# Processor.net
KiCad netlist of a schematic drawn in Altium Designer
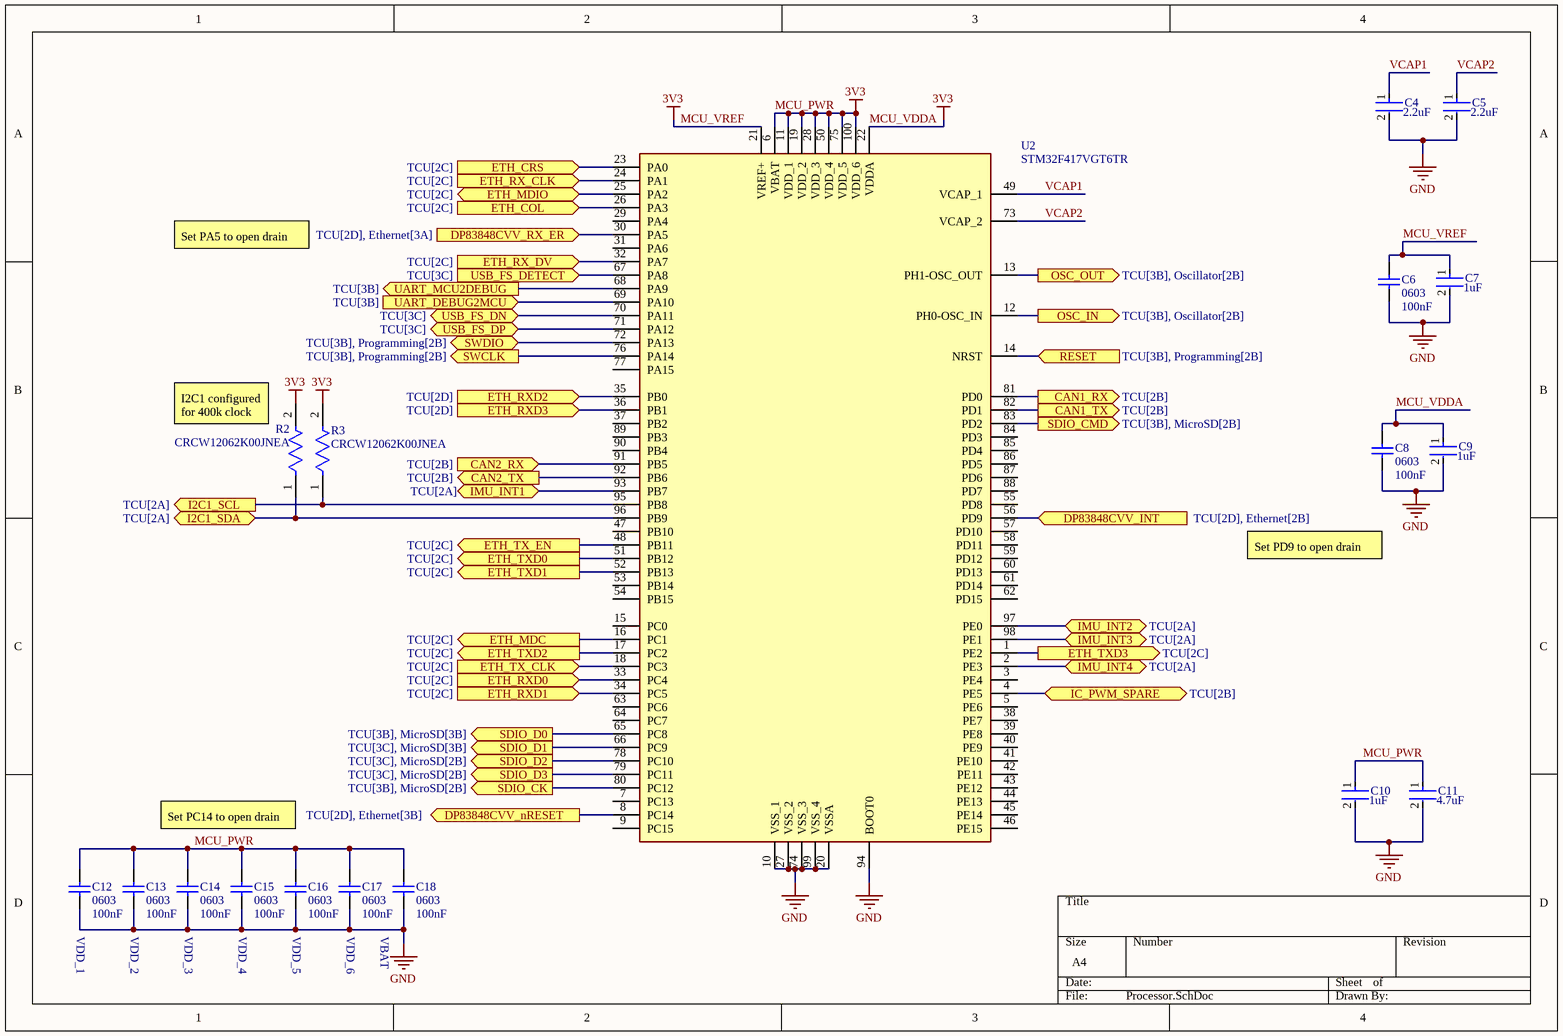
[diagram p0: Processor.SchDoc]

(export (version "E")
  (design (tool "Eeschema 10.0.6"))
  (components
    (comp (ref "C4")
      (value "C0603C225K4PACTU")
      (footprint "FP-C0603C225K4PACTU-MFG")
      (description "CAP CER 2.2UF 16V X5R 0603")
      (fields
        (field (name "CAPACITANCE") "2.2uF")
        (field (name "TOLERANCE") "10%")
        (field (name "VOLTAGE") "16V")
      )
      (libsource (lib "Altium Content Vault") (part "b4654b650e69147ec39a6b967a45e02"))
    )
    (comp (ref "C5")
      (value "C0603C225K4PACTU")
      (footprint "FP-C0603C225K4PACTU-MFG")
      (description "CAP CER 2.2UF 16V X5R 0603")
      (fields
        (field (name "CAPACITANCE") "2.2uF")
        (field (name "TOLERANCE") "10%")
        (field (name "VOLTAGE") "16V")
      )
      (libsource (lib "Altium Content Vault") (part "b4654b650e69147ec39a6b967a45e02"))
    )
    (comp (ref "C6")
      (value "C0603X104K5RACTU")
      (footprint "CAPC1608X87X35NL15T15")
      (fields
        (field (name "MANUFACTURER") "Kemet")
        (field (name "CASE CODE (IMPERIAL)") "0603")
        (field (name "CAPACITANCE") "100nF")
        (field (name "TOLERANCE") "10%")
        (field (name "VOLTAGE") "50V")
      )
      (libsource (lib "Altium Content Vault") (part "CAP"))
    )
    (comp (ref "C7")
      (value "CL10A105KA8NNNC")
      (footprint "FP-CL10-IPC_C")
      (description "Cap Ceramic 1uF 25V X5R ±10% Pad SMD 0603 +85°C T/R")
      (fields
        (field (name "CAPACITANCE") "1uF")
        (field (name "VOLTAGE") "25V")
        (field (name "TOLERANCE") "10%")
      )
      (libsource (lib "Altium Content Vault") (part "b4654b650e69147ec39a6b967a45e02"))
    )
    (comp (ref "C8")
      (value "C0603X104K5RACTU")
      (footprint "CAPC1608X87X35NL15T15")
      (fields
        (field (name "MANUFACTURER") "Kemet")
        (field (name "CASE CODE (IMPERIAL)") "0603")
        (field (name "CAPACITANCE") "100nF")
        (field (name "TOLERANCE") "10%")
        (field (name "VOLTAGE") "50V")
      )
      (libsource (lib "Altium Content Vault") (part "CAP"))
    )
    (comp (ref "C9")
      (value "CL10A105KA8NNNC")
      (footprint "FP-CL10-IPC_C")
      (description "Cap Ceramic 1uF 25V X5R ±10% Pad SMD 0603 +85°C T/R")
      (fields
        (field (name "CAPACITANCE") "1uF")
        (field (name "VOLTAGE") "25V")
        (field (name "TOLERANCE") "10%")
      )
      (libsource (lib "Altium Content Vault") (part "b4654b650e69147ec39a6b967a45e02"))
    )
    (comp (ref "C10")
      (value "CL10A105KA8NNNC")
      (footprint "FP-CL10-IPC_C")
      (description "Cap Ceramic 1uF 25V X5R ±10% Pad SMD 0603 +85°C T/R")
      (fields
        (field (name "CAPACITANCE") "1uF")
        (field (name "VOLTAGE") "25V")
        (field (name "TOLERANCE") "10%")
      )
      (libsource (lib "Altium Content Vault") (part "b4654b650e69147ec39a6b967a45e02"))
    )
    (comp (ref "C11")
      (value "C1005X5R1A475K050BC")
      (footprint "FP-C1005-050-0_15-MFG")
      (description "CAP CER 4.7UF 10V X5R 0402")
      (fields (field (name "TOLERANCE") "10%") (field (name "CAPACITANCE") "4.7uF"))
      (libsource (lib "Altium Content Vault") (part "b4654b650e69147ec39a6b967a45e02"))
    )
    (comp (ref "C12")
      (value "C0603X104K5RACTU")
      (footprint "CAPC1608X87X35NL15T15")
      (fields
        (field (name "MANUFACTURER") "Kemet")
        (field (name "CASE CODE (IMPERIAL)") "0603")
        (field (name "CAPACITANCE") "100nF")
        (field (name "TOLERANCE") "10%")
        (field (name "VOLTAGE") "50V")
      )
      (libsource (lib "Altium Content Vault") (part "CAP"))
    )
    (comp (ref "C13")
      (value "C0603X104K5RACTU")
      (footprint "CAPC1608X87X35NL15T15")
      (fields
        (field (name "MANUFACTURER") "Kemet")
        (field (name "CASE CODE (IMPERIAL)") "0603")
        (field (name "CAPACITANCE") "100nF")
        (field (name "TOLERANCE") "10%")
        (field (name "VOLTAGE") "50V")
      )
      (libsource (lib "Altium Content Vault") (part "CAP"))
    )
    (comp (ref "C14")
      (value "C0603X104K5RACTU")
      (footprint "CAPC1608X87X35NL15T15")
      (fields
        (field (name "MANUFACTURER") "Kemet")
        (field (name "CASE CODE (IMPERIAL)") "0603")
        (field (name "CAPACITANCE") "100nF")
        (field (name "TOLERANCE") "10%")
        (field (name "VOLTAGE") "50V")
      )
      (libsource (lib "Altium Content Vault") (part "CAP"))
    )
    (comp (ref "C15")
      (value "C0603X104K5RACTU")
      (footprint "CAPC1608X87X35NL15T15")
      (fields
        (field (name "MANUFACTURER") "Kemet")
        (field (name "CASE CODE (IMPERIAL)") "0603")
        (field (name "CAPACITANCE") "100nF")
        (field (name "TOLERANCE") "10%")
        (field (name "VOLTAGE") "50V")
      )
      (libsource (lib "Altium Content Vault") (part "CAP"))
    )
    (comp (ref "C16")
      (value "C0603X104K5RACTU")
      (footprint "CAPC1608X87X35NL15T15")
      (fields
        (field (name "MANUFACTURER") "Kemet")
        (field (name "CASE CODE (IMPERIAL)") "0603")
        (field (name "CAPACITANCE") "100nF")
        (field (name "TOLERANCE") "10%")
        (field (name "VOLTAGE") "50V")
      )
      (libsource (lib "Altium Content Vault") (part "CAP"))
    )
    (comp (ref "C17")
      (value "C0603X104K5RACTU")
      (footprint "CAPC1608X87X35NL15T15")
      (fields
        (field (name "MANUFACTURER") "Kemet")
        (field (name "CASE CODE (IMPERIAL)") "0603")
        (field (name "CAPACITANCE") "100nF")
        (field (name "TOLERANCE") "10%")
        (field (name "VOLTAGE") "50V")
      )
      (libsource (lib "Altium Content Vault") (part "CAP"))
    )
    (comp (ref "C18")
      (value "C0603X104K5RACTU")
      (footprint "CAPC1608X87X35NL15T15")
      (fields
        (field (name "MANUFACTURER") "Kemet")
        (field (name "CASE CODE (IMPERIAL)") "0603")
        (field (name "CAPACITANCE") "100nF")
        (field (name "TOLERANCE") "10%")
        (field (name "VOLTAGE") "50V")
      )
      (libsource (lib "Altium Content Vault") (part "CAP"))
    )
    (comp (ref "R2")
      (value "CRCW12062K00JNEA")
      (footprint "FP-CRCW1206-e3-IPC_B")
      (description "RES Thick Film, 2kΩ, 5%, 0.25W, 200ppm/°C, 1206")
      (fields (field (name "TOLERANCE") "5%"))
      (libsource (lib "Altium Content Vault") (part "1029c3af85768c4190bb7ad29bc67b5"))
    )
    (comp (ref "R3")
      (value "CRCW12062K00JNEA")
      (footprint "FP-CRCW1206-e3-IPC_B")
      (description "RES Thick Film, 2kΩ, 5%, 0.25W, 200ppm/°C, 1206")
      (fields (field (name "TOLERANCE") "5%"))
      (libsource (lib "Altium Content Vault") (part "1029c3af85768c4190bb7ad29bc67b5"))
    )
    (comp (ref "U2")
      (value "STM32F417VGT6TR")
      (footprint "STM-LQFP100_N")
      (description "RISC Microcontroller, 32-Bit, FLASH, CORTEX-M4 CPU, 168MHz, CMOS, PQFP100")
      (fields (field (name "MANUFACTURER") "STMicroelectronics"))
      (libsource (lib "Microcontrollers") (part "STM32F417VGT6TR"))
    )
  )
  (nets
    (net (code "1") (name "/CAN1_RX") (class "Default")
      (node (ref "U2") (pin "81") (pinfunction "PD0_81") (pintype "passive"))
    )
    (net (code "2") (name "/CAN1_TX") (class "Default")
      (node (ref "U2") (pin "82") (pinfunction "PD1_82") (pintype "passive"))
    )
    (net (code "3") (name "/CAN2_RX") (class "Default")
      (node (ref "U2") (pin "91") (pinfunction "PB5_91") (pintype "passive"))
    )
    (net (code "4") (name "/CAN2_TX") (class "Default")
      (node (ref "U2") (pin "92") (pinfunction "PB6_92") (pintype "passive"))
    )
    (net (code "5") (name "/DP83848CVV_INT") (class "Default")
      (node (ref "U2") (pin "56") (pinfunction "PD9_56") (pintype "passive"))
    )
    (net (code "6") (name "/DP83848CVV_RX_ER") (class "Default")
      (node (ref "U2") (pin "30") (pinfunction "PA5_30") (pintype "passive"))
    )
    (net (code "7") (name "/DP83848CVV_nRESET") (class "Default")
      (node (ref "U2") (pin "8") (pinfunction "PC14_8") (pintype "passive"))
    )
    (net (code "8") (name "/ETH_COL") (class "Default")
      (node (ref "U2") (pin "26") (pinfunction "PA3_26") (pintype "passive"))
    )
    (net (code "9") (name "/ETH_CRS") (class "Default")
      (node (ref "U2") (pin "23") (pinfunction "PA0_23") (pintype "passive"))
    )
    (net (code "10") (name "/ETH_MDC") (class "Default")
      (node (ref "U2") (pin "16") (pinfunction "PC1_16") (pintype "passive"))
    )
    (net (code "11") (name "/ETH_MDIO") (class "Default")
      (node (ref "U2") (pin "25") (pinfunction "PA2_25") (pintype "passive"))
    )
    (net (code "12") (name "/ETH_RXD0") (class "Default")
      (node (ref "U2") (pin "33") (pinfunction "PC4_33") (pintype "passive"))
    )
    (net (code "13") (name "/ETH_RXD1") (class "Default")
      (node (ref "U2") (pin "34") (pinfunction "PC5_34") (pintype "passive"))
    )
    (net (code "14") (name "/ETH_RXD2") (class "Default")
      (node (ref "U2") (pin "35") (pinfunction "PB0_35") (pintype "passive"))
    )
    (net (code "15") (name "/ETH_RXD3") (class "Default")
      (node (ref "U2") (pin "36") (pinfunction "PB1_36") (pintype "passive"))
    )
    (net (code "16") (name "/ETH_RX_CLK") (class "Default")
      (node (ref "U2") (pin "24") (pinfunction "PA1_24") (pintype "passive"))
    )
    (net (code "17") (name "/ETH_RX_DV") (class "Default")
      (node (ref "U2") (pin "32") (pinfunction "PA7_32") (pintype "passive"))
    )
    (net (code "18") (name "/ETH_TXD0") (class "Default")
      (node (ref "U2") (pin "51") (pinfunction "PB12_51") (pintype "passive"))
    )
    (net (code "19") (name "/ETH_TXD1") (class "Default")
      (node (ref "U2") (pin "52") (pinfunction "PB13_52") (pintype "passive"))
    )
    (net (code "20") (name "/ETH_TXD2") (class "Default")
      (node (ref "U2") (pin "17") (pinfunction "PC2_17") (pintype "passive"))
    )
    (net (code "21") (name "/ETH_TXD3") (class "Default")
      (node (ref "U2") (pin "1") (pinfunction "PE2_1") (pintype "passive"))
    )
    (net (code "22") (name "/ETH_TX_CLK") (class "Default")
      (node (ref "U2") (pin "18") (pinfunction "PC3_18") (pintype "passive"))
    )
    (net (code "23") (name "/ETH_TX_EN") (class "Default")
      (node (ref "U2") (pin "48") (pinfunction "PB11_48") (pintype "passive"))
    )
    (net (code "24") (name "/I2C1_SCL") (class "Default")
      (node (ref "R3") (pin "1") (pinfunction "1_1") (pintype "passive"))
      (node (ref "U2") (pin "95") (pinfunction "PB8_95") (pintype "passive"))
    )
    (net (code "25") (name "/I2C1_SDA") (class "Default")
      (node (ref "R2") (pin "1") (pinfunction "1_1") (pintype "passive"))
      (node (ref "U2") (pin "96") (pinfunction "PB9_96") (pintype "passive"))
    )
    (net (code "26") (name "/IC_PWM_SPARE") (class "Default")
      (node (ref "U2") (pin "4") (pinfunction "PE5_4") (pintype "passive"))
    )
    (net (code "27") (name "/IMU_INT1") (class "Default")
      (node (ref "U2") (pin "93") (pinfunction "PB7_93") (pintype "passive"))
    )
    (net (code "28") (name "/IMU_INT2") (class "Default")
      (node (ref "U2") (pin "97") (pinfunction "PE0_97") (pintype "passive"))
    )
    (net (code "29") (name "/IMU_INT3") (class "Default")
      (node (ref "U2") (pin "98") (pinfunction "PE1_98") (pintype "passive"))
    )
    (net (code "30") (name "/IMU_INT4") (class "Default")
      (node (ref "U2") (pin "2") (pinfunction "PE3_2") (pintype "passive"))
    )
    (net (code "31") (name "/OSC_IN") (class "Default")
      (node (ref "U2") (pin "12") (pinfunction "PH0-OSC_IN_12") (pintype "passive"))
    )
    (net (code "32") (name "/OSC_OUT") (class "Default")
      (node (ref "U2") (pin "13") (pinfunction "PH1-OSC_OUT_13") (pintype "passive"))
    )
    (net (code "33") (name "/RESET") (class "Default")
      (node (ref "U2") (pin "14") (pinfunction "NRST_14") (pintype "passive"))
    )
    (net (code "34") (name "/SDIO_CK") (class "Default")
      (node (ref "U2") (pin "80") (pinfunction "PC12_80") (pintype "passive"))
    )
    (net (code "35") (name "/SDIO_CMD") (class "Default")
      (node (ref "U2") (pin "83") (pinfunction "PD2_83") (pintype "passive"))
    )
    (net (code "36") (name "/SDIO_D0") (class "Default")
      (node (ref "U2") (pin "65") (pinfunction "PC8_65") (pintype "passive"))
    )
    (net (code "37") (name "/SDIO_D1") (class "Default")
      (node (ref "U2") (pin "66") (pinfunction "PC9_66") (pintype "passive"))
    )
    (net (code "38") (name "/SDIO_D2") (class "Default")
      (node (ref "U2") (pin "78") (pinfunction "PC10_78") (pintype "passive"))
    )
    (net (code "39") (name "/SDIO_D3") (class "Default")
      (node (ref "U2") (pin "79") (pinfunction "PC11_79") (pintype "passive"))
    )
    (net (code "40") (name "/SWCLK") (class "Default")
      (node (ref "U2") (pin "76") (pinfunction "PA14_76") (pintype "passive"))
    )
    (net (code "41") (name "/SWDIO") (class "Default")
      (node (ref "U2") (pin "72") (pinfunction "PA13_72") (pintype "passive"))
    )
    (net (code "42") (name "/UART_DEBUG2MCU") (class "Default")
      (node (ref "U2") (pin "69") (pinfunction "PA10_69") (pintype "passive"))
    )
    (net (code "43") (name "/UART_MCU2DEBUG") (class "Default")
      (node (ref "U2") (pin "68") (pinfunction "PA9_68") (pintype "passive"))
    )
    (net (code "44") (name "/USB_FS_DETECT") (class "Default")
      (node (ref "U2") (pin "67") (pinfunction "PA8_67") (pintype "passive"))
    )
    (net (code "45") (name "/USB_FS_DN") (class "Default")
      (node (ref "U2") (pin "70") (pinfunction "PA11_70") (pintype "passive"))
    )
    (net (code "46") (name "/USB_FS_DP") (class "Default")
      (node (ref "U2") (pin "71") (pinfunction "PA12_71") (pintype "passive"))
    )
    (net (code "47") (name "/VCAP1") (class "Default")
      (node (ref "C4") (pin "1") (pinfunction "1_1") (pintype "passive"))
      (node (ref "U2") (pin "49") (pinfunction "VCAP_1_49") (pintype "passive"))
    )
    (net (code "48") (name "/VCAP2") (class "Default")
      (node (ref "C5") (pin "1") (pinfunction "1_1") (pintype "passive"))
      (node (ref "U2") (pin "73") (pinfunction "VCAP_2_73") (pintype "passive"))
    )
    (net (code "49") (name "3V3") (class "Default")
      (node (ref "C10") (pin "1") (pinfunction "1_1") (pintype "passive"))
      (node (ref "C11") (pin "1") (pinfunction "1_1") (pintype "passive"))
      (node (ref "C12") (pin "2") (pinfunction "2_2") (pintype "passive"))
      (node (ref "C13") (pin "2") (pinfunction "2_2") (pintype "passive"))
      (node (ref "C14") (pin "2") (pinfunction "2_2") (pintype "passive"))
      (node (ref "C15") (pin "2") (pinfunction "2_2") (pintype "passive"))
      (node (ref "C16") (pin "2") (pinfunction "2_2") (pintype "passive"))
      (node (ref "C17") (pin "2") (pinfunction "2_2") (pintype "passive"))
      (node (ref "C18") (pin "2") (pinfunction "2_2") (pintype "passive"))
      (node (ref "C6") (pin "1") (pinfunction "1_1") (pintype "passive"))
      (node (ref "C7") (pin "1") (pinfunction "1_1") (pintype "passive"))
      (node (ref "C8") (pin "1") (pinfunction "1_1") (pintype "passive"))
      (node (ref "C9") (pin "1") (pinfunction "1_1") (pintype "passive"))
      (node (ref "R2") (pin "2") (pinfunction "2_2") (pintype "passive"))
      (node (ref "R3") (pin "2") (pinfunction "2_2") (pintype "passive"))
      (node (ref "U2") (pin "100") (pinfunction "VDD_6_100") (pintype "passive"))
      (node (ref "U2") (pin "11") (pinfunction "VDD_1_11") (pintype "passive"))
      (node (ref "U2") (pin "19") (pinfunction "VDD_2_19") (pintype "passive"))
      (node (ref "U2") (pin "21") (pinfunction "VREF+_21") (pintype "passive"))
      (node (ref "U2") (pin "22") (pinfunction "VDDA_22") (pintype "passive"))
      (node (ref "U2") (pin "28") (pinfunction "VDD_3_28") (pintype "passive"))
      (node (ref "U2") (pin "50") (pinfunction "VDD_4_50") (pintype "passive"))
      (node (ref "U2") (pin "6") (pinfunction "VBAT_6") (pintype "passive"))
      (node (ref "U2") (pin "75") (pinfunction "VDD_5_75") (pintype "passive"))
    )
    (net (code "50") (name "GND") (class "Default")
      (node (ref "C10") (pin "2") (pinfunction "2_2") (pintype "passive"))
      (node (ref "C11") (pin "2") (pinfunction "2_2") (pintype "passive"))
      (node (ref "C12") (pin "1") (pinfunction "1_1") (pintype "passive"))
      (node (ref "C13") (pin "1") (pinfunction "1_1") (pintype "passive"))
      (node (ref "C14") (pin "1") (pinfunction "1_1") (pintype "passive"))
      (node (ref "C15") (pin "1") (pinfunction "1_1") (pintype "passive"))
      (node (ref "C16") (pin "1") (pinfunction "1_1") (pintype "passive"))
      (node (ref "C17") (pin "1") (pinfunction "1_1") (pintype "passive"))
      (node (ref "C18") (pin "1") (pinfunction "1_1") (pintype "passive"))
      (node (ref "C4") (pin "2") (pinfunction "2_2") (pintype "passive"))
      (node (ref "C5") (pin "2") (pinfunction "2_2") (pintype "passive"))
      (node (ref "C6") (pin "2") (pinfunction "2_2") (pintype "passive"))
      (node (ref "C7") (pin "2") (pinfunction "2_2") (pintype "passive"))
      (node (ref "C8") (pin "2") (pinfunction "2_2") (pintype "passive"))
      (node (ref "C9") (pin "2") (pinfunction "2_2") (pintype "passive"))
      (node (ref "U2") (pin "10") (pinfunction "VSS_1_10") (pintype "passive"))
      (node (ref "U2") (pin "20") (pinfunction "VSSA_20") (pintype "passive"))
      (node (ref "U2") (pin "27") (pinfunction "VSS_2_27") (pintype "passive"))
      (node (ref "U2") (pin "74") (pinfunction "VSS_3_74") (pintype "passive"))
      (node (ref "U2") (pin "94") (pinfunction "BOOT0_94") (pintype "passive"))
      (node (ref "U2") (pin "99") (pinfunction "VSS_4_99") (pintype "passive"))
    )
    (net (code "51") (name "unconnected-(U2-PA4-Pad29)") (class "Default")
      (node (ref "U2") (pin "29") (pinfunction "PA4_29") (pintype "passive"))
    )
    (net (code "52") (name "unconnected-(U2-PA6-Pad31)") (class "Default")
      (node (ref "U2") (pin "31") (pinfunction "PA6_31") (pintype "passive"))
    )
    (net (code "53") (name "unconnected-(U2-PA15-Pad77)") (class "Default")
      (node (ref "U2") (pin "77") (pinfunction "PA15_77") (pintype "passive"))
    )
    (net (code "54") (name "unconnected-(U2-PB2-Pad37)") (class "Default")
      (node (ref "U2") (pin "37") (pinfunction "PB2_37") (pintype "passive"))
    )
    (net (code "55") (name "unconnected-(U2-PB3-Pad89)") (class "Default")
      (node (ref "U2") (pin "89") (pinfunction "PB3_89") (pintype "passive"))
    )
    (net (code "56") (name "unconnected-(U2-PB4-Pad90)") (class "Default")
      (node (ref "U2") (pin "90") (pinfunction "PB4_90") (pintype "passive"))
    )
    (net (code "57") (name "unconnected-(U2-PB10-Pad47)") (class "Default")
      (node (ref "U2") (pin "47") (pinfunction "PB10_47") (pintype "passive"))
    )
    (net (code "58") (name "unconnected-(U2-PB14-Pad53)") (class "Default")
      (node (ref "U2") (pin "53") (pinfunction "PB14_53") (pintype "passive"))
    )
    (net (code "59") (name "unconnected-(U2-PB15-Pad54)") (class "Default")
      (node (ref "U2") (pin "54") (pinfunction "PB15_54") (pintype "passive"))
    )
    (net (code "60") (name "unconnected-(U2-PC0-Pad15)") (class "Default")
      (node (ref "U2") (pin "15") (pinfunction "PC0_15") (pintype "passive"))
    )
    (net (code "61") (name "unconnected-(U2-PC6-Pad63)") (class "Default")
      (node (ref "U2") (pin "63") (pinfunction "PC6_63") (pintype "passive"))
    )
    (net (code "62") (name "unconnected-(U2-PC7-Pad64)") (class "Default")
      (node (ref "U2") (pin "64") (pinfunction "PC7_64") (pintype "passive"))
    )
    (net (code "63") (name "unconnected-(U2-PC13-Pad7)") (class "Default")
      (node (ref "U2") (pin "7") (pinfunction "PC13_7") (pintype "passive"))
    )
    (net (code "64") (name "unconnected-(U2-PC15-Pad9)") (class "Default")
      (node (ref "U2") (pin "9") (pinfunction "PC15_9") (pintype "passive"))
    )
    (net (code "65") (name "unconnected-(U2-PD3-Pad84)") (class "Default")
      (node (ref "U2") (pin "84") (pinfunction "PD3_84") (pintype "passive"))
    )
    (net (code "66") (name "unconnected-(U2-PD4-Pad85)") (class "Default")
      (node (ref "U2") (pin "85") (pinfunction "PD4_85") (pintype "passive"))
    )
    (net (code "67") (name "unconnected-(U2-PD5-Pad86)") (class "Default")
      (node (ref "U2") (pin "86") (pinfunction "PD5_86") (pintype "passive"))
    )
    (net (code "68") (name "unconnected-(U2-PD6-Pad87)") (class "Default")
      (node (ref "U2") (pin "87") (pinfunction "PD6_87") (pintype "passive"))
    )
    (net (code "69") (name "unconnected-(U2-PD7-Pad88)") (class "Default")
      (node (ref "U2") (pin "88") (pinfunction "PD7_88") (pintype "passive"))
    )
    (net (code "70") (name "unconnected-(U2-PD8-Pad55)") (class "Default")
      (node (ref "U2") (pin "55") (pinfunction "PD8_55") (pintype "passive"))
    )
    (net (code "71") (name "unconnected-(U2-PD10-Pad57)") (class "Default")
      (node (ref "U2") (pin "57") (pinfunction "PD10_57") (pintype "passive"))
    )
    (net (code "72") (name "unconnected-(U2-PD11-Pad58)") (class "Default")
      (node (ref "U2") (pin "58") (pinfunction "PD11_58") (pintype "passive"))
    )
    (net (code "73") (name "unconnected-(U2-PD12-Pad59)") (class "Default")
      (node (ref "U2") (pin "59") (pinfunction "PD12_59") (pintype "passive"))
    )
    (net (code "74") (name "unconnected-(U2-PD13-Pad60)") (class "Default")
      (node (ref "U2") (pin "60") (pinfunction "PD13_60") (pintype "passive"))
    )
    (net (code "75") (name "unconnected-(U2-PD14-Pad61)") (class "Default")
      (node (ref "U2") (pin "61") (pinfunction "PD14_61") (pintype "passive"))
    )
    (net (code "76") (name "unconnected-(U2-PD15-Pad62)") (class "Default")
      (node (ref "U2") (pin "62") (pinfunction "PD15_62") (pintype "passive"))
    )
    (net (code "77") (name "unconnected-(U2-PE4-Pad3)") (class "Default")
      (node (ref "U2") (pin "3") (pinfunction "PE4_3") (pintype "passive"))
    )
    (net (code "78") (name "unconnected-(U2-PE6-Pad5)") (class "Default")
      (node (ref "U2") (pin "5") (pinfunction "PE6_5") (pintype "passive"))
    )
    (net (code "79") (name "unconnected-(U2-PE7-Pad38)") (class "Default")
      (node (ref "U2") (pin "38") (pinfunction "PE7_38") (pintype "passive"))
    )
    (net (code "80") (name "unconnected-(U2-PE8-Pad39)") (class "Default")
      (node (ref "U2") (pin "39") (pinfunction "PE8_39") (pintype "passive"))
    )
    (net (code "81") (name "unconnected-(U2-PE9-Pad40)") (class "Default")
      (node (ref "U2") (pin "40") (pinfunction "PE9_40") (pintype "passive"))
    )
    (net (code "82") (name "unconnected-(U2-PE10-Pad41)") (class "Default")
      (node (ref "U2") (pin "41") (pinfunction "PE10_41") (pintype "passive"))
    )
    (net (code "83") (name "unconnected-(U2-PE11-Pad42)") (class "Default")
      (node (ref "U2") (pin "42") (pinfunction "PE11_42") (pintype "passive"))
    )
    (net (code "84") (name "unconnected-(U2-PE12-Pad43)") (class "Default")
      (node (ref "U2") (pin "43") (pinfunction "PE12_43") (pintype "passive"))
    )
    (net (code "85") (name "unconnected-(U2-PE13-Pad44)") (class "Default")
      (node (ref "U2") (pin "44") (pinfunction "PE13_44") (pintype "passive"))
    )
    (net (code "86") (name "unconnected-(U2-PE14-Pad45)") (class "Default")
      (node (ref "U2") (pin "45") (pinfunction "PE14_45") (pintype "passive"))
    )
    (net (code "87") (name "unconnected-(U2-PE15-Pad46)") (class "Default")
      (node (ref "U2") (pin "46") (pinfunction "PE15_46") (pintype "passive"))
    )
  )
)
